# Telemetria_Oficial.net
KiCad netlist of a schematic drawn in Altium Designer
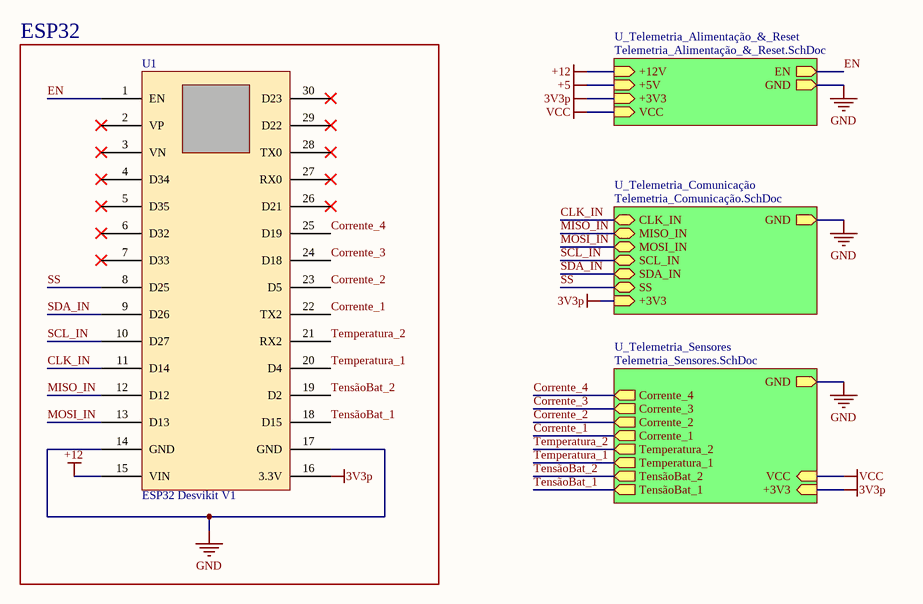
[diagram p0: Telemetria_Oficial.SchDoc]

(export (version "E")
  (design (tool "Eeschema 10.0.6"))
  (components
    (comp (ref "U1")
      (value "ESP32 Desvikit V1")
      (footprint "ESP32_Desvikit_v1")
      (description "microcontrolador com moculo bluethoth e wifi")
      (fields (field (name "Comment") "microcontrolador"))
      (libsource (lib "Sinaliza玢o_Official") (part "ESP32 Desvikit v1"))
    )
  )
  (nets
    (net (code "2") (name "+12") (class "Default")
      (node (ref "U1") (pin "15") (pinfunction "VIN_15") (pintype "passive"))
    )
    (net (code "3") (name "/CLK_IN") (class "Default")
      (node (ref "U1") (pin "11") (pinfunction "D14_11") (pintype "passive"))
    )
    (net (code "4") (name "/Corrente_1") (class "Default")
      (node (ref "U1") (pin "22") (pinfunction "TX2_22") (pintype "passive"))
    )
    (net (code "5") (name "/Corrente_2") (class "Default")
      (node (ref "U1") (pin "23") (pinfunction "D5_23") (pintype "passive"))
    )
    (net (code "6") (name "/Corrente_3") (class "Default")
      (node (ref "U1") (pin "24") (pinfunction "D18_24") (pintype "passive"))
    )
    (net (code "7") (name "/Corrente_4") (class "Default")
      (node (ref "U1") (pin "25") (pinfunction "D19_25") (pintype "passive"))
    )
    (net (code "8") (name "/EN") (class "Default")
      (node (ref "U1") (pin "1") (pinfunction "EN_1") (pintype "passive"))
    )
    (net (code "9") (name "/MISO_IN") (class "Default")
      (node (ref "U1") (pin "12") (pinfunction "D12_12") (pintype "passive"))
    )
    (net (code "10") (name "/MOSI_IN") (class "Default")
      (node (ref "U1") (pin "13") (pinfunction "D13_13") (pintype "passive"))
    )
    (net (code "11") (name "/SCL_IN") (class "Default")
      (node (ref "U1") (pin "10") (pinfunction "D27_10") (pintype "passive"))
    )
    (net (code "12") (name "/SDA_IN") (class "Default")
      (node (ref "U1") (pin "9") (pinfunction "D26_9") (pintype "passive"))
    )
    (net (code "13") (name "/SS") (class "Default")
      (node (ref "U1") (pin "8") (pinfunction "D25_8") (pintype "passive"))
    )
    (net (code "14") (name "/Temperatura_1") (class "Default")
      (node (ref "U1") (pin "20") (pinfunction "D4_20") (pintype "passive"))
    )
    (net (code "15") (name "/Temperatura_2") (class "Default")
      (node (ref "U1") (pin "21") (pinfunction "RX2_21") (pintype "passive"))
    )
    (net (code "16") (name "/TensãoBat_1") (class "Default")
      (node (ref "U1") (pin "18") (pinfunction "D15_18") (pintype "passive"))
    )
    (net (code "17") (name "/TensãoBat_2") (class "Default")
      (node (ref "U1") (pin "19") (pinfunction "D2_19") (pintype "passive"))
    )
    (net (code "18") (name "3V3p") (class "Default")
      (node (ref "U1") (pin "16") (pinfunction "3.3V_16") (pintype "passive"))
    )
    (net (code "19") (name "GND") (class "Default")
      (node (ref "U1") (pin "14") (pinfunction "GND_14") (pintype "passive"))
      (node (ref "U1") (pin "17") (pinfunction "GND_17") (pintype "passive"))
    )
    (net (code "21") (name "unconnected-(U1-D21-Pad26)") (class "Default")
      (node (ref "U1") (pin "26") (pinfunction "D21_26") (pintype "passive+no_connect"))
    )
    (net (code "22") (name "unconnected-(U1-D22-Pad29)") (class "Default")
      (node (ref "U1") (pin "29") (pinfunction "D22_29") (pintype "passive+no_connect"))
    )
    (net (code "23") (name "unconnected-(U1-D23-Pad30)") (class "Default")
      (node (ref "U1") (pin "30") (pinfunction "D23_30") (pintype "passive+no_connect"))
    )
    (net (code "24") (name "unconnected-(U1-D32-Pad6)") (class "Default")
      (node (ref "U1") (pin "6") (pinfunction "D32_6") (pintype "passive+no_connect"))
    )
    (net (code "25") (name "unconnected-(U1-D33-Pad7)") (class "Default")
      (node (ref "U1") (pin "7") (pinfunction "D33_7") (pintype "passive+no_connect"))
    )
    (net (code "26") (name "unconnected-(U1-D34-Pad4)") (class "Default")
      (node (ref "U1") (pin "4") (pinfunction "D34_4") (pintype "passive+no_connect"))
    )
    (net (code "27") (name "unconnected-(U1-D35-Pad5)") (class "Default")
      (node (ref "U1") (pin "5") (pinfunction "D35_5") (pintype "passive+no_connect"))
    )
    (net (code "28") (name "unconnected-(U1-RX0-Pad27)") (class "Default")
      (node (ref "U1") (pin "27") (pinfunction "RX0_27") (pintype "passive+no_connect"))
    )
    (net (code "29") (name "unconnected-(U1-TX0-Pad28)") (class "Default")
      (node (ref "U1") (pin "28") (pinfunction "TX0_28") (pintype "passive+no_connect"))
    )
    (net (code "30") (name "unconnected-(U1-VN-Pad3)") (class "Default")
      (node (ref "U1") (pin "3") (pinfunction "VN_3") (pintype "passive+no_connect"))
    )
    (net (code "31") (name "unconnected-(U1-VP-Pad2)") (class "Default")
      (node (ref "U1") (pin "2") (pinfunction "VP_2") (pintype "passive+no_connect"))
    )
  )
)
